# SCH_555Egiant_2025-03-13.net
KiCad netlist of a schematic drawn in EasyEDA
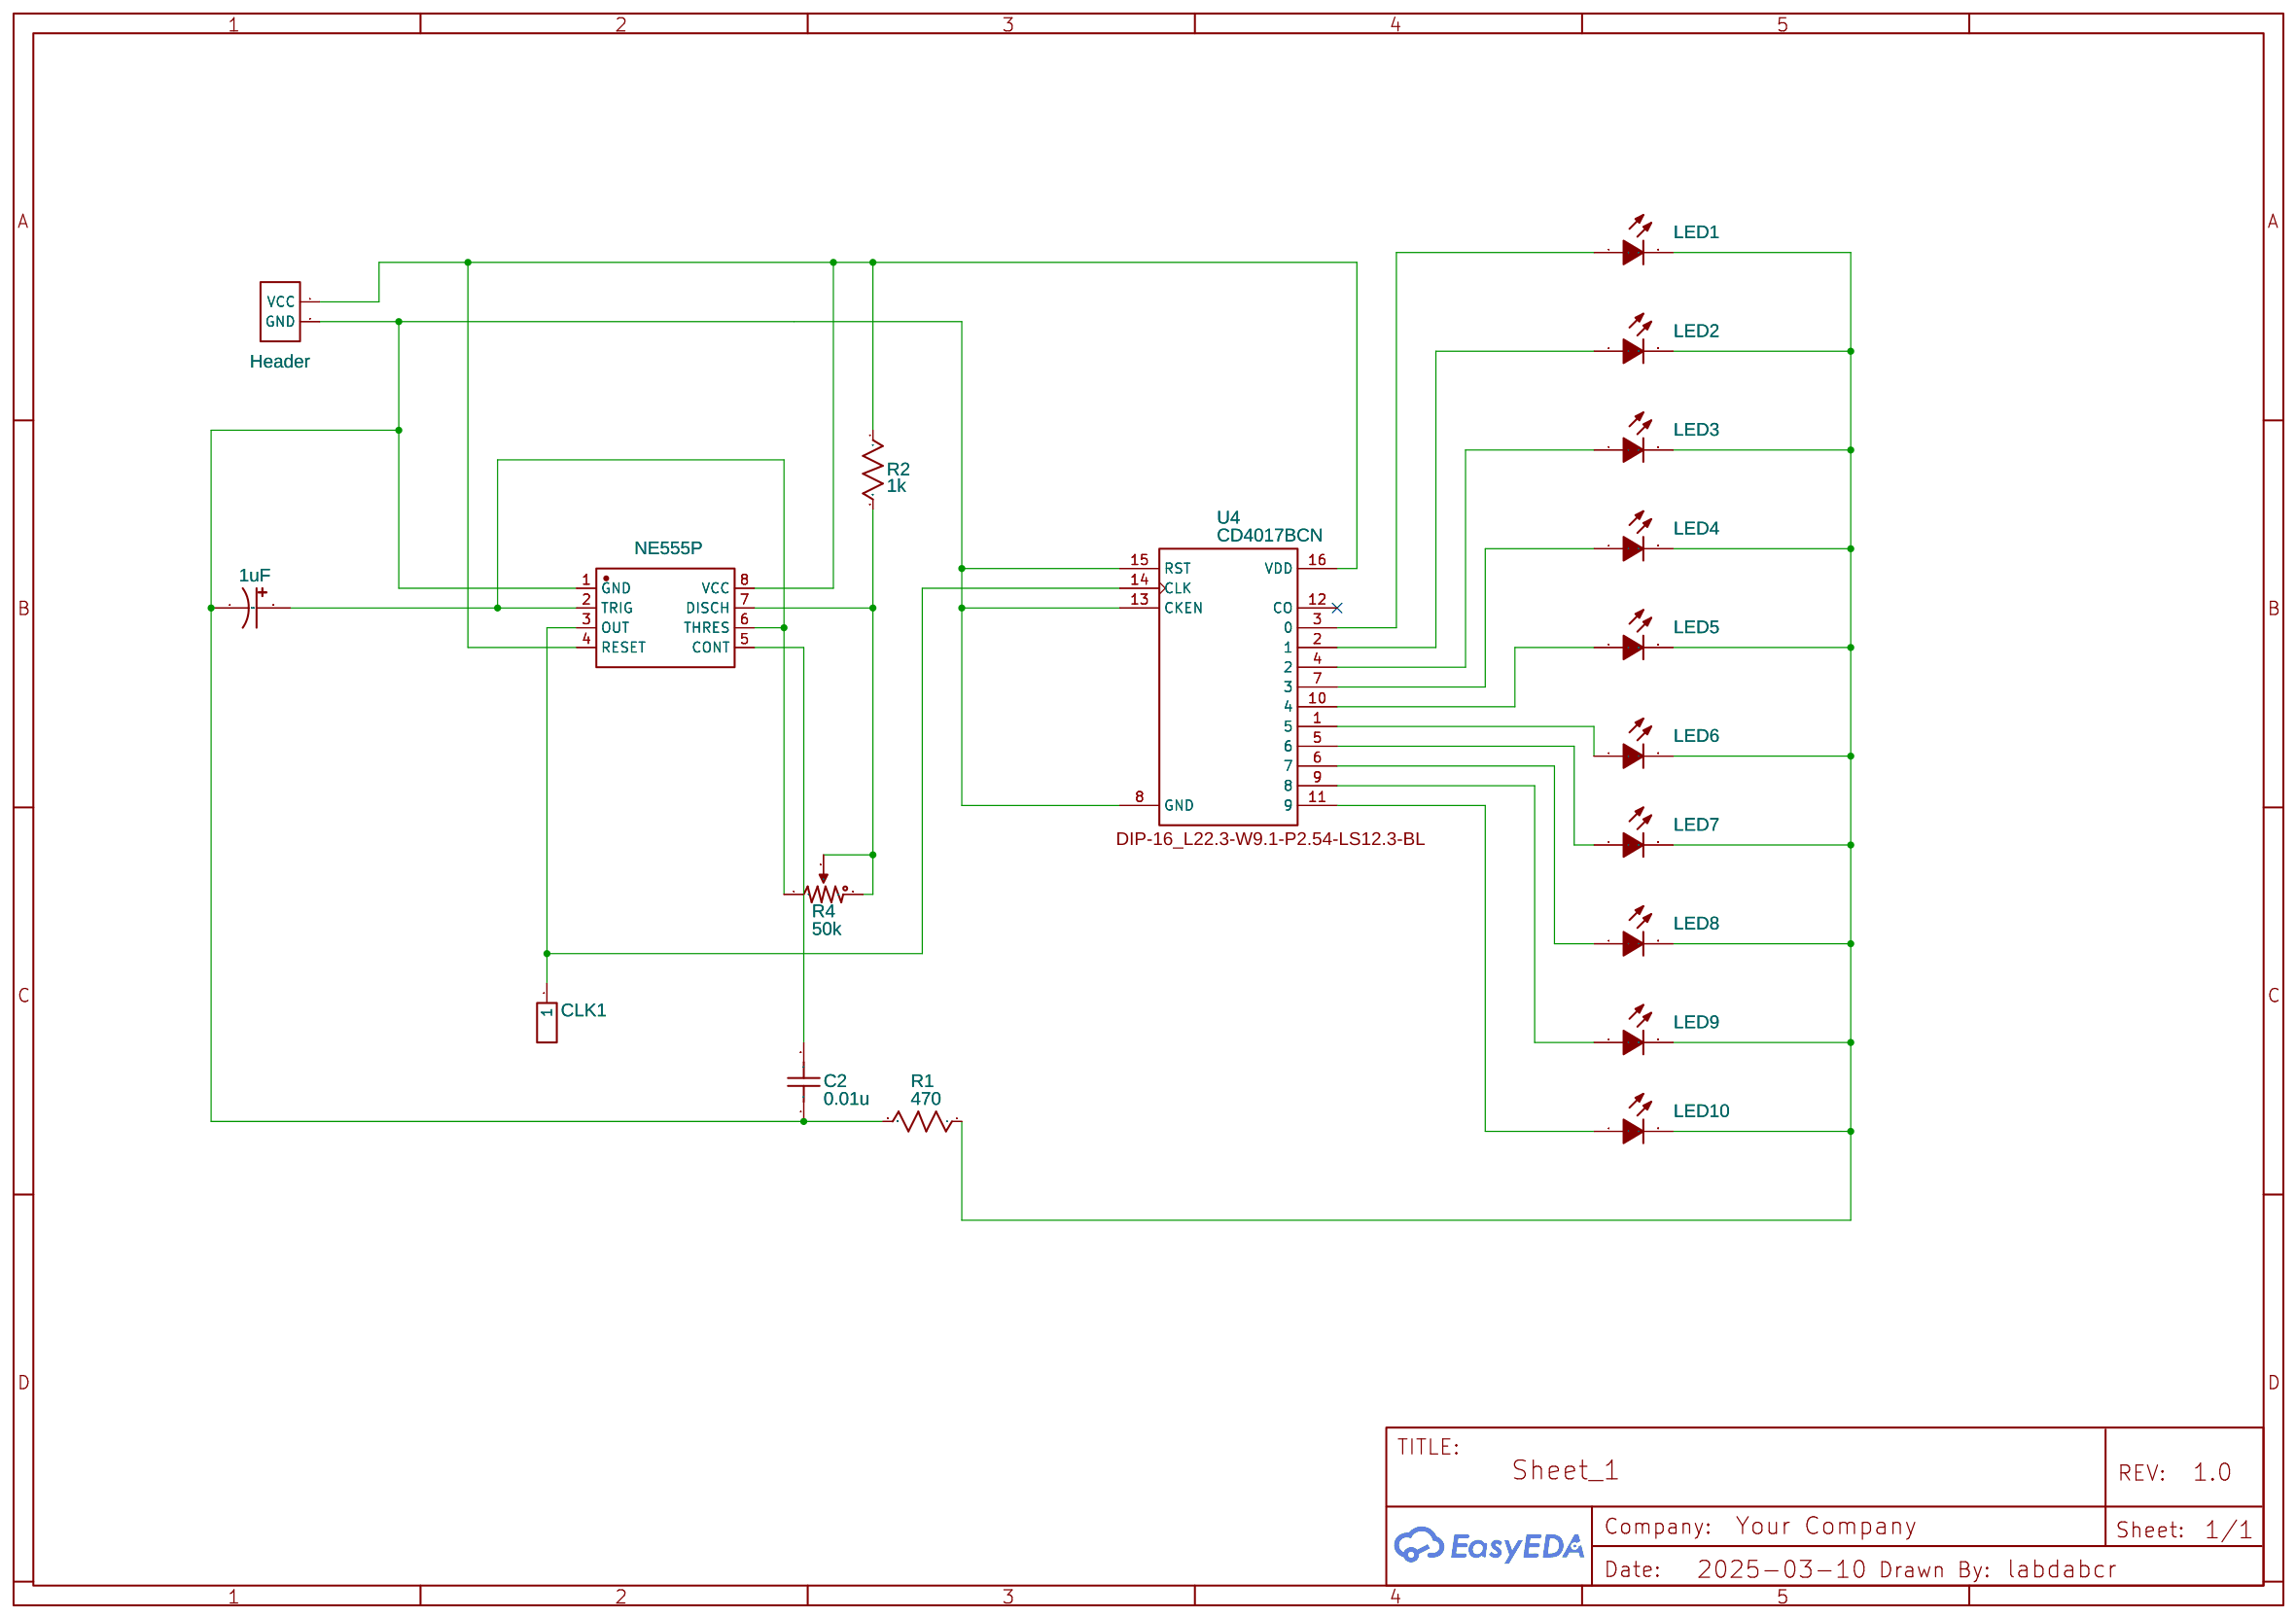
[diagram p0: schematic sheet]

(export (version "E")
  (design (tool "Eeschema 10.0.6"))
  (components
    (comp (ref "C1")
      (value "1uF")
      (fields (field (name "Manufacturer Part") "UVZ1H010MDD") (field (name "Manufacturer") "Nichicon(尼吉康)"))
      (libsource (lib "") (part "UVZ1H010MDD"))
    )
    (comp (ref "C2") (value "0.01u") (libsource (lib "") (part "C_0603_US")))
    (comp (ref "CLK1")
      (value "C81276")
      (fields
        (field (name "Manufacturer Part") "2.54-1*1P针")
        (field (name "Manufacturer") "BOOMELE(Boom Precision Elec)")
      )
      (libsource (lib "") (part "Header-Male-2.54_1x1"))
    )
    (comp (ref "H1") (value "Header") (libsource (lib "") (part "HEADER-FEMALE-2.54_1X2")))
    (comp (ref "LED1") (value "LED_5MM") (libsource (lib "") (part "LED_5MM")))
    (comp (ref "LED2") (value "LED_5MM") (libsource (lib "") (part "LED_5MM")))
    (comp (ref "LED3") (value "LED_5MM") (libsource (lib "") (part "LED_5MM")))
    (comp (ref "LED4") (value "LED_5MM") (libsource (lib "") (part "LED_5MM")))
    (comp (ref "LED5") (value "LED_5MM") (libsource (lib "") (part "LED_5MM")))
    (comp (ref "LED6") (value "LED_5MM") (libsource (lib "") (part "LED_5MM")))
    (comp (ref "LED7") (value "LED_5MM") (libsource (lib "") (part "LED_5MM")))
    (comp (ref "LED8") (value "LED_5MM") (libsource (lib "") (part "LED_5MM")))
    (comp (ref "LED9") (value "LED_5MM") (libsource (lib "") (part "LED_5MM")))
    (comp (ref "LED10") (value "LED_5MM") (libsource (lib "") (part "LED_5MM")))
    (comp (ref "R1")
      (value "470")
      (fields (field (name "Manufacturer Part") "?"))
      (libsource (lib "") (part "Resistor_1"))
    )
    (comp (ref "R2")
      (value "1k")
      (fields (field (name "Manufacturer Part") "?"))
      (libsource (lib "") (part "Resistor"))
    )
    (comp (ref "R4")
      (value "50k")
      (fields (field (name "Manufacturer Part") "?"))
      (libsource (lib "") (part "Potentiometer"))
    )
    (comp (ref "U2")
      (value "NE555P")
      (fields (field (name "Manufacturer") "TI(德州仪器)"))
      (libsource (lib "") (part "NE555P"))
    )
    (comp (ref "U4") (value "CD4017BCN") (libsource (lib "") (part "CD4017BCN")))
  )
  (nets
    (net (code "1") (name "Net-(H1-GND)") (class "Default")
      (node (ref "C1") (pin "2") (pinfunction "2_2") (pintype "unspecified"))
      (node (ref "C2") (pin "1") (pinfunction "1_1") (pintype "unspecified"))
      (node (ref "H1") (pin "2") (pinfunction "GND_2") (pintype "unspecified"))
      (node (ref "R1") (pin "2") (pinfunction "2_2") (pintype "unspecified"))
      (node (ref "U2") (pin "1") (pinfunction "GND_1") (pintype "unspecified"))
      (node (ref "U4") (pin "13") (pinfunction "CKEN_13") (pintype "unspecified"))
      (node (ref "U4") (pin "15") (pinfunction "RST_15") (pintype "unspecified"))
      (node (ref "U4") (pin "8") (pinfunction "GND_8") (pintype "passive"))
    )
    (net (code "2") (name "Net-(H1-VCC)") (class "Default")
      (node (ref "H1") (pin "1") (pinfunction "VCC_1") (pintype "unspecified"))
      (node (ref "R2") (pin "1") (pinfunction "1_1") (pintype "unspecified"))
      (node (ref "U2") (pin "4") (pinfunction "RESET_4") (pintype "unspecified"))
      (node (ref "U2") (pin "8") (pinfunction "VCC_8") (pintype "unspecified"))
      (node (ref "U4") (pin "16") (pinfunction "VDD_16") (pintype "passive"))
    )
    (net (code "3") (name "Net-(LED1-A)") (class "Default")
      (node (ref "LED1") (pin "1") (pinfunction "A_1") (pintype "input"))
      (node (ref "U4") (pin "3") (pinfunction "0_3") (pintype "output"))
    )
    (net (code "4") (name "Net-(LED1-K)") (class "Default")
      (node (ref "LED1") (pin "2") (pinfunction "K_2") (pintype "input"))
      (node (ref "LED10") (pin "2") (pinfunction "K_2") (pintype "input"))
      (node (ref "LED2") (pin "2") (pinfunction "K_2") (pintype "input"))
      (node (ref "LED3") (pin "2") (pinfunction "K_2") (pintype "input"))
      (node (ref "LED4") (pin "2") (pinfunction "K_2") (pintype "input"))
      (node (ref "LED5") (pin "2") (pinfunction "K_2") (pintype "input"))
      (node (ref "LED6") (pin "2") (pinfunction "K_2") (pintype "input"))
      (node (ref "LED7") (pin "2") (pinfunction "K_2") (pintype "input"))
      (node (ref "LED8") (pin "2") (pinfunction "K_2") (pintype "input"))
      (node (ref "LED9") (pin "2") (pinfunction "K_2") (pintype "input"))
      (node (ref "R1") (pin "1") (pinfunction "1_1") (pintype "unspecified"))
    )
    (net (code "5") (name "Net-(LED2-A)") (class "Default")
      (node (ref "LED2") (pin "1") (pinfunction "A_1") (pintype "input"))
      (node (ref "U4") (pin "2") (pinfunction "1_2") (pintype "output"))
    )
    (net (code "6") (name "Net-(LED3-A)") (class "Default")
      (node (ref "LED3") (pin "1") (pinfunction "A_1") (pintype "input"))
      (node (ref "U4") (pin "4") (pinfunction "2_4") (pintype "output"))
    )
    (net (code "7") (name "Net-(LED4-A)") (class "Default")
      (node (ref "LED4") (pin "1") (pinfunction "A_1") (pintype "input"))
      (node (ref "U4") (pin "7") (pinfunction "3_7") (pintype "output"))
    )
    (net (code "8") (name "Net-(LED5-A)") (class "Default")
      (node (ref "LED5") (pin "1") (pinfunction "A_1") (pintype "input"))
      (node (ref "U4") (pin "10") (pinfunction "4_10") (pintype "output"))
    )
    (net (code "9") (name "Net-(LED6-A)") (class "Default")
      (node (ref "LED6") (pin "1") (pinfunction "A_1") (pintype "input"))
      (node (ref "U4") (pin "1") (pinfunction "5_1") (pintype "output"))
    )
    (net (code "10") (name "Net-(LED7-A)") (class "Default")
      (node (ref "LED7") (pin "1") (pinfunction "A_1") (pintype "input"))
      (node (ref "U4") (pin "5") (pinfunction "6_5") (pintype "output"))
    )
    (net (code "11") (name "Net-(LED8-A)") (class "Default")
      (node (ref "LED8") (pin "1") (pinfunction "A_1") (pintype "input"))
      (node (ref "U4") (pin "6") (pinfunction "7_6") (pintype "output"))
    )
    (net (code "12") (name "Net-(LED9-A)") (class "Default")
      (node (ref "LED9") (pin "1") (pinfunction "A_1") (pintype "input"))
      (node (ref "U4") (pin "9") (pinfunction "8_9") (pintype "output"))
    )
    (net (code "13") (name "Net-(LED10-A)") (class "Default")
      (node (ref "LED10") (pin "1") (pinfunction "A_1") (pintype "input"))
      (node (ref "U4") (pin "11") (pinfunction "9_11") (pintype "output"))
    )
    (net (code "14") (name "Net-(R4-2)") (class "Default")
      (node (ref "R2") (pin "2") (pinfunction "2_2") (pintype "unspecified"))
      (node (ref "R4") (pin "2") (pinfunction "3_2") (pintype "unspecified"))
      (node (ref "R4") (pin "3") (pinfunction "2_3") (pintype "unspecified"))
      (node (ref "U2") (pin "7") (pinfunction "DISCH_7") (pintype "unspecified"))
    )
    (net (code "15") (name "Net-(U2-CONT)") (class "Default")
      (node (ref "C2") (pin "2") (pinfunction "2_2") (pintype "unspecified"))
      (node (ref "U2") (pin "5") (pinfunction "CONT_5") (pintype "unspecified"))
    )
    (net (code "16") (name "Net-(U2-OUT)") (class "Default")
      (node (ref "CLK1") (pin "1") (pinfunction "1_1") (pintype "unspecified"))
      (node (ref "U2") (pin "3") (pinfunction "OUT_3") (pintype "unspecified"))
      (node (ref "U4") (pin "14") (pinfunction "CLK_14") (pintype "unspecified"))
    )
    (net (code "17") (name "Net-(U2-THRES)") (class "Default")
      (node (ref "C1") (pin "1") (pinfunction "1_1") (pintype "unspecified"))
      (node (ref "R4") (pin "1") (pinfunction "1_1") (pintype "unspecified"))
      (node (ref "U2") (pin "2") (pinfunction "TRIG_2") (pintype "unspecified"))
      (node (ref "U2") (pin "6") (pinfunction "THRES_6") (pintype "unspecified"))
    )
    (net (code "18") (name "unconnected-(U4-CO-Pad12)") (class "Default")
      (node (ref "U4") (pin "12") (pinfunction "CO_12") (pintype "output+no_connect"))
    )
  )
)
